# SCH_Pathfinder-V1_2025-10-25.net
KiCad netlist of a schematic drawn in EasyEDA
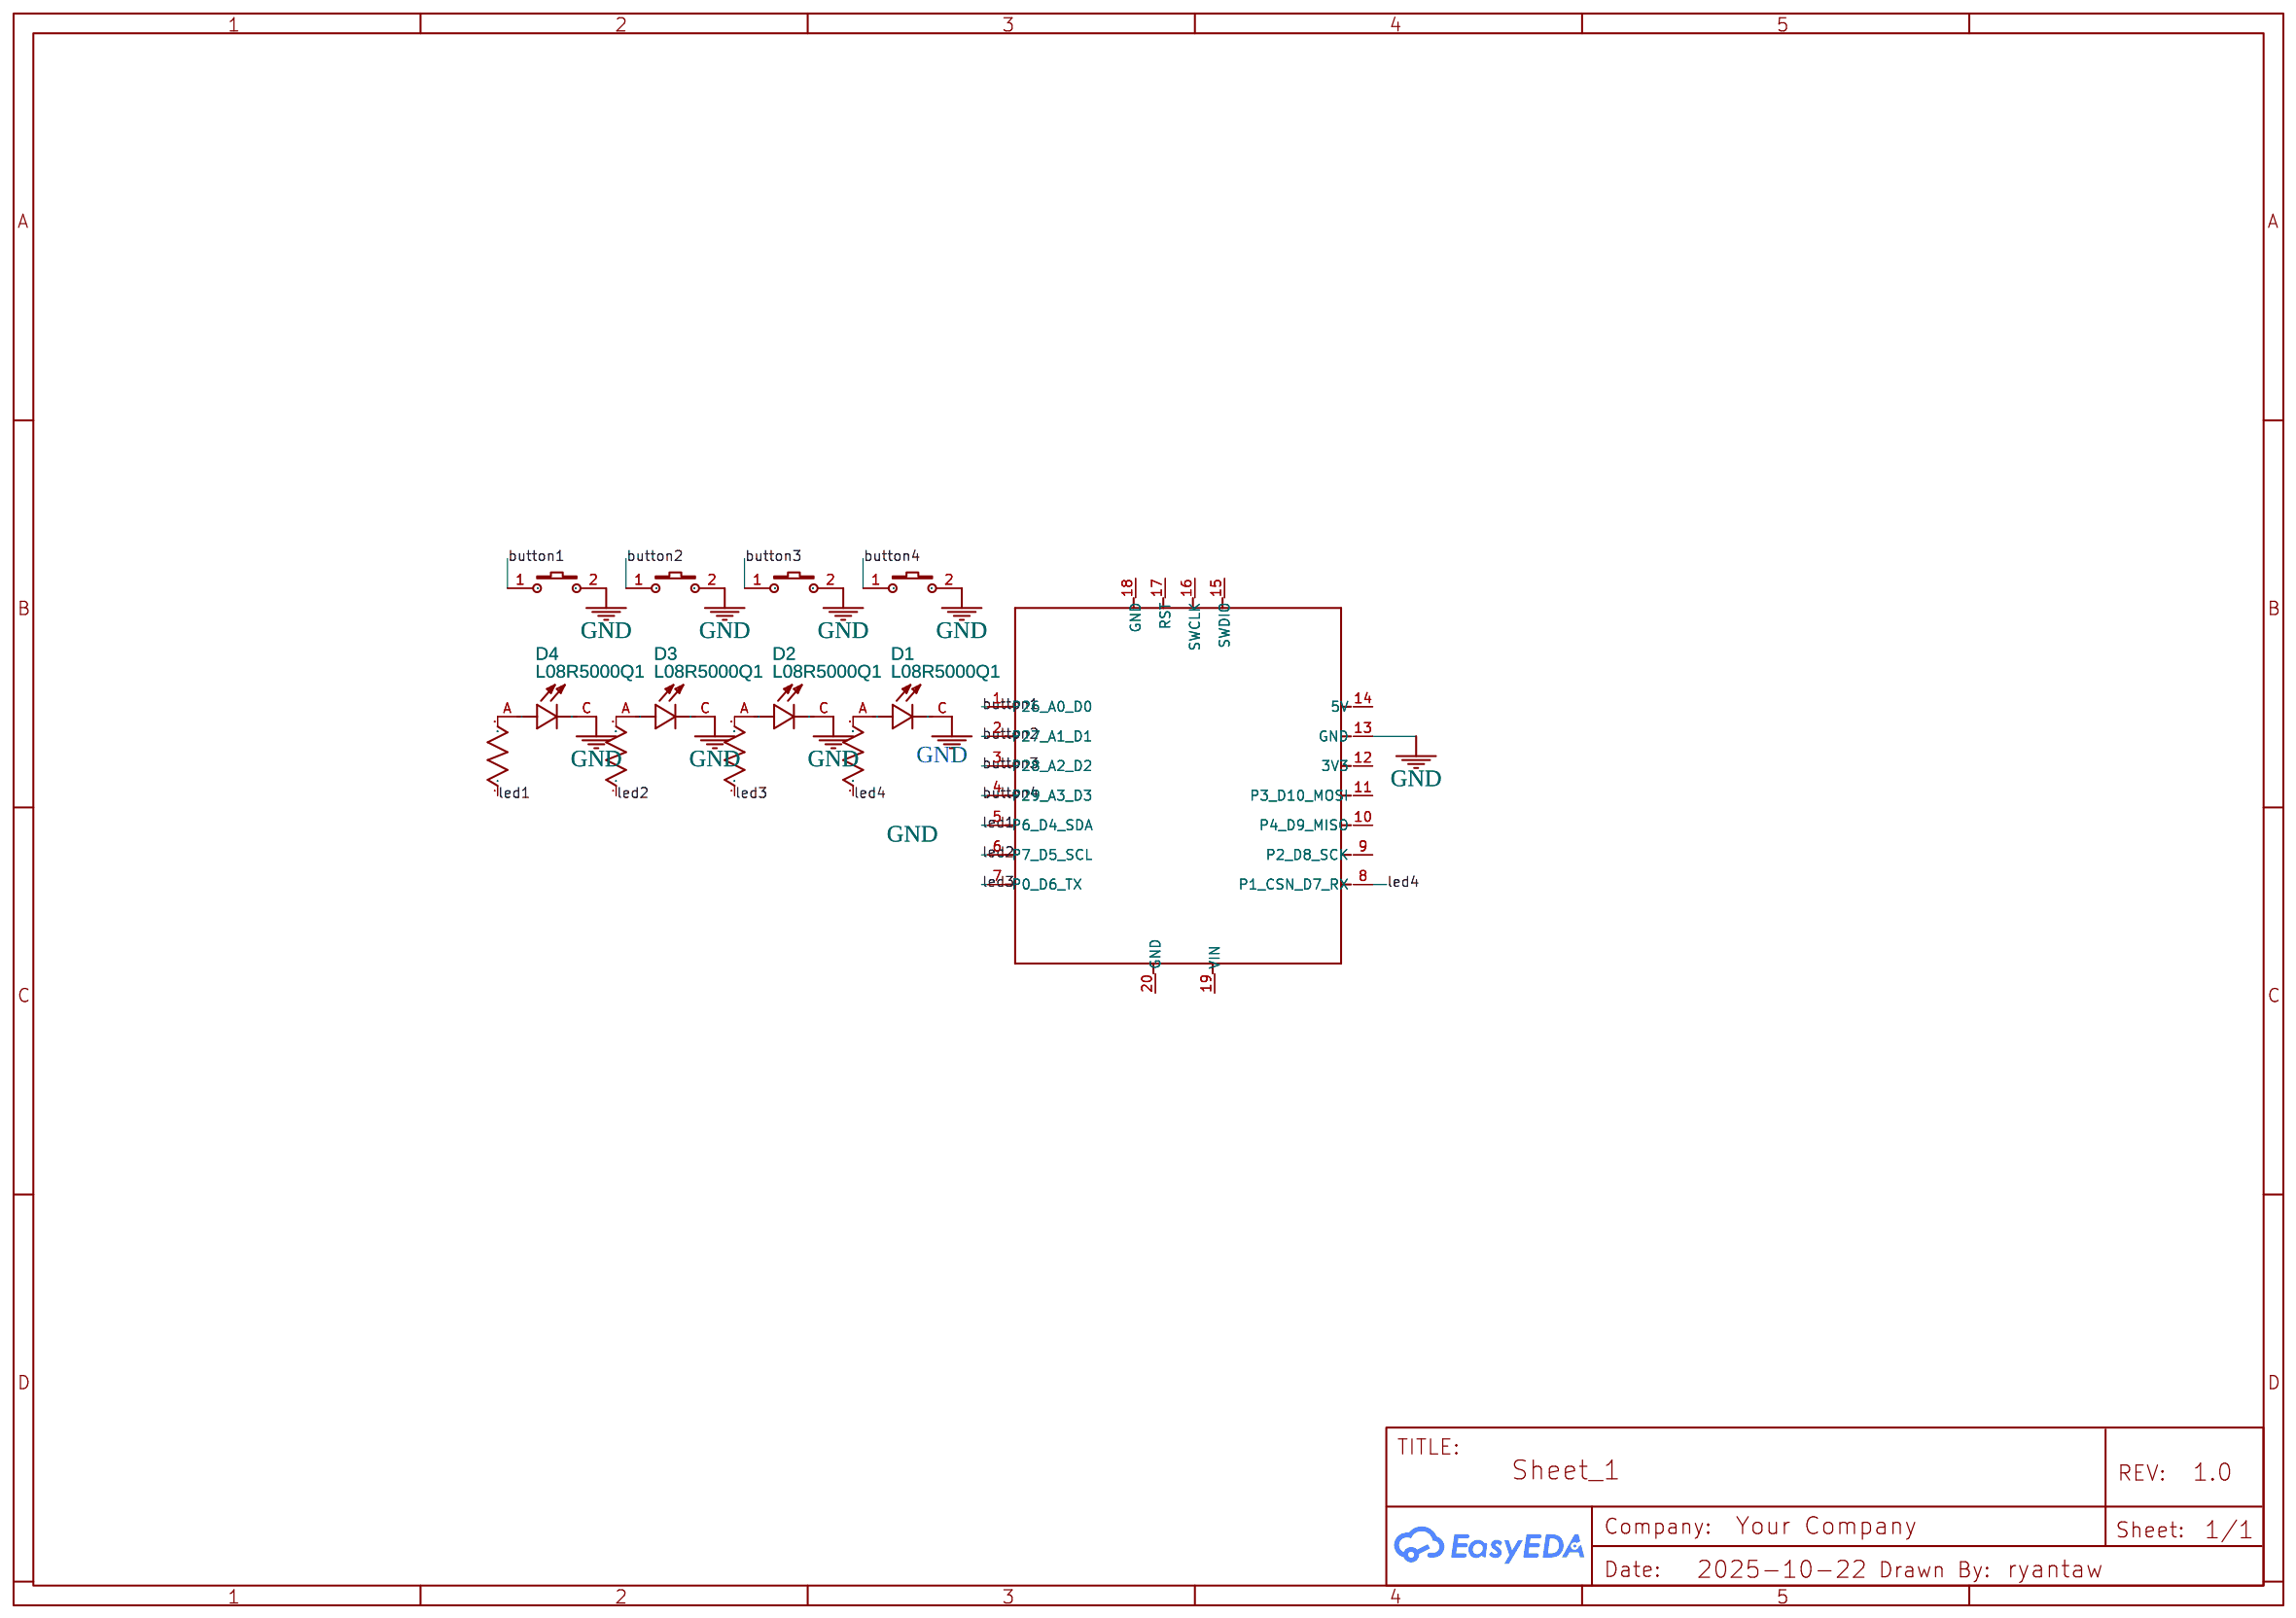
[diagram p0: schematic sheet]

(export (version "E")
  (design (tool "Eeschema 10.0.6"))
  (components
    (comp (ref "D1") (value "L08R5000Q1") (libsource (lib "") (part "L08R5000Q1")))
    (comp (ref "D2") (value "L08R5000Q1") (libsource (lib "") (part "L08R5000Q1")))
    (comp (ref "D3") (value "L08R5000Q1") (libsource (lib "") (part "L08R5000Q1")))
    (comp (ref "D4") (value "L08R5000Q1") (libsource (lib "") (part "L08R5000Q1")))
    (comp (ref "KEY1")
      (value "K2-3.6×6.1_SMD")
      (fields (field (name "Manufacturer Part") "K2-1107ST-A4SW-06"))
      (libsource (lib "") (part "K2-3.6×6.1_SMD"))
    )
    (comp (ref "KEY2")
      (value "K2-3.6×6.1_SMD")
      (fields (field (name "Manufacturer Part") "K2-1107ST-A4SW-06"))
      (libsource (lib "") (part "K2-3.6×6.1_SMD"))
    )
    (comp (ref "KEY3")
      (value "K2-3.6×6.1_SMD")
      (fields (field (name "Manufacturer Part") "K2-1107ST-A4SW-06"))
      (libsource (lib "") (part "K2-3.6×6.1_SMD"))
    )
    (comp (ref "KEY4")
      (value "K2-3.6×6.1_SMD")
      (fields (field (name "Manufacturer Part") "K2-1107ST-A4SW-06"))
      (libsource (lib "") (part "K2-3.6×6.1_SMD"))
    )
    (comp (ref "R1") (value "1k") (libsource (lib "") (part "R_0603_US")))
    (comp (ref "R2") (value "1k") (libsource (lib "") (part "R_0603_US")))
    (comp (ref "R3") (value "1k") (libsource (lib "") (part "R_0603_US")))
    (comp (ref "R4") (value "1k") (libsource (lib "") (part "R_0603_US")))
    (comp (ref "U1") (value "XIAO-RP2040") (libsource (lib "") (part "XIAO-RP2040")))
  )
  (nets
    (net (code "1") (name "/button1") (class "Default")
      (node (ref "KEY1") (pin "1") (pinfunction "1_1") (pintype "unspecified"))
      (node (ref "U1") (pin "1") (pinfunction "P26_A0_D0_1") (pintype "bidirectional"))
    )
    (net (code "2") (name "/button2") (class "Default")
      (node (ref "KEY2") (pin "1") (pinfunction "1_1") (pintype "unspecified"))
      (node (ref "U1") (pin "2") (pinfunction "P27_A1_D1_2") (pintype "bidirectional"))
    )
    (net (code "3") (name "/button3") (class "Default")
      (node (ref "KEY3") (pin "1") (pinfunction "1_1") (pintype "unspecified"))
      (node (ref "U1") (pin "3") (pinfunction "P28_A2_D2_3") (pintype "bidirectional"))
    )
    (net (code "4") (name "/button4") (class "Default")
      (node (ref "KEY4") (pin "1") (pinfunction "1_1") (pintype "unspecified"))
      (node (ref "U1") (pin "4") (pinfunction "P29_A3_D3_4") (pintype "bidirectional"))
    )
    (net (code "5") (name "/led1") (class "Default")
      (node (ref "R1") (pin "1") (pinfunction "1_1") (pintype "unspecified"))
      (node (ref "U1") (pin "5") (pinfunction "P6_D4_SDA_5") (pintype "bidirectional"))
    )
    (net (code "6") (name "/led2") (class "Default")
      (node (ref "R2") (pin "1") (pinfunction "1_1") (pintype "unspecified"))
      (node (ref "U1") (pin "6") (pinfunction "P7_D5_SCL_6") (pintype "bidirectional"))
    )
    (net (code "7") (name "/led3") (class "Default")
      (node (ref "R3") (pin "1") (pinfunction "1_1") (pintype "unspecified"))
      (node (ref "U1") (pin "7") (pinfunction "P0_D6_TX_7") (pintype "bidirectional"))
    )
    (net (code "8") (name "/led4") (class "Default")
      (node (ref "R4") (pin "1") (pinfunction "1_1") (pintype "unspecified"))
      (node (ref "U1") (pin "8") (pinfunction "P1_CSN_D7_RX_8") (pintype "bidirectional"))
    )
    (net (code "9") (name "GND") (class "Default")
      (node (ref "D1") (pin "C") (pinfunction "C_C") (pintype "bidirectional"))
      (node (ref "D2") (pin "C") (pinfunction "C_C") (pintype "bidirectional"))
      (node (ref "D3") (pin "C") (pinfunction "C_C") (pintype "bidirectional"))
      (node (ref "D4") (pin "C") (pinfunction "C_C") (pintype "bidirectional"))
      (node (ref "KEY1") (pin "2") (pinfunction "2_2") (pintype "unspecified"))
      (node (ref "KEY2") (pin "2") (pinfunction "2_2") (pintype "unspecified"))
      (node (ref "KEY3") (pin "2") (pinfunction "2_2") (pintype "unspecified"))
      (node (ref "KEY4") (pin "2") (pinfunction "2_2") (pintype "unspecified"))
      (node (ref "U1") (pin "13") (pinfunction "GND_13") (pintype "bidirectional"))
    )
    (net (code "10") (name "Net-(D1-PadA)") (class "Default")
      (node (ref "D1") (pin "A") (pinfunction "A_A") (pintype "bidirectional"))
      (node (ref "R4") (pin "2") (pinfunction "2_2") (pintype "unspecified"))
    )
    (net (code "11") (name "Net-(D2-PadA)") (class "Default")
      (node (ref "D2") (pin "A") (pinfunction "A_A") (pintype "bidirectional"))
      (node (ref "R3") (pin "2") (pinfunction "2_2") (pintype "unspecified"))
    )
    (net (code "12") (name "Net-(D3-PadA)") (class "Default")
      (node (ref "D3") (pin "A") (pinfunction "A_A") (pintype "bidirectional"))
      (node (ref "R2") (pin "2") (pinfunction "2_2") (pintype "unspecified"))
    )
    (net (code "13") (name "Net-(D4-PadA)") (class "Default")
      (node (ref "D4") (pin "A") (pinfunction "A_A") (pintype "bidirectional"))
      (node (ref "R1") (pin "2") (pinfunction "2_2") (pintype "unspecified"))
    )
    (net (code "14") (name "unconnected-(U1-3V3-Pad12)") (class "Default")
      (node (ref "U1") (pin "12") (pinfunction "3V3_12") (pintype "bidirectional"))
    )
    (net (code "15") (name "unconnected-(U1-5V-Pad14)") (class "Default")
      (node (ref "U1") (pin "14") (pinfunction "5V_14") (pintype "bidirectional"))
    )
    (net (code "16") (name "unconnected-(U1-GND-Pad18)") (class "Default")
      (node (ref "U1") (pin "18") (pinfunction "GND_18") (pintype "bidirectional"))
    )
    (net (code "17") (name "unconnected-(U1-GND-Pad20)") (class "Default")
      (node (ref "U1") (pin "20") (pinfunction "GND_20") (pintype "bidirectional"))
    )
    (net (code "18") (name "unconnected-(U1-P2_D8_SCK-Pad9)") (class "Default")
      (node (ref "U1") (pin "9") (pinfunction "P2_D8_SCK_9") (pintype "bidirectional"))
    )
    (net (code "19") (name "unconnected-(U1-P3_D10_MOSI-Pad11)") (class "Default")
      (node (ref "U1") (pin "11") (pinfunction "P3_D10_MOSI_11") (pintype "bidirectional"))
    )
    (net (code "20") (name "unconnected-(U1-P4_D9_MISO-Pad10)") (class "Default")
      (node (ref "U1") (pin "10") (pinfunction "P4_D9_MISO_10") (pintype "bidirectional"))
    )
    (net (code "21") (name "unconnected-(U1-RST-Pad17)") (class "Default")
      (node (ref "U1") (pin "17") (pinfunction "RST_17") (pintype "bidirectional"))
    )
    (net (code "22") (name "unconnected-(U1-SWCLK-Pad16)") (class "Default")
      (node (ref "U1") (pin "16") (pinfunction "SWCLK_16") (pintype "bidirectional"))
    )
    (net (code "23") (name "unconnected-(U1-SWDIO-Pad15)") (class "Default")
      (node (ref "U1") (pin "15") (pinfunction "SWDIO_15") (pintype "bidirectional"))
    )
    (net (code "24") (name "unconnected-(U1-VIN-Pad19)") (class "Default")
      (node (ref "U1") (pin "19") (pinfunction "VIN_19") (pintype "bidirectional"))
    )
  )
)
